# RM_LM25116.net
KiCad netlist of a schematic drawn in Altium Designer
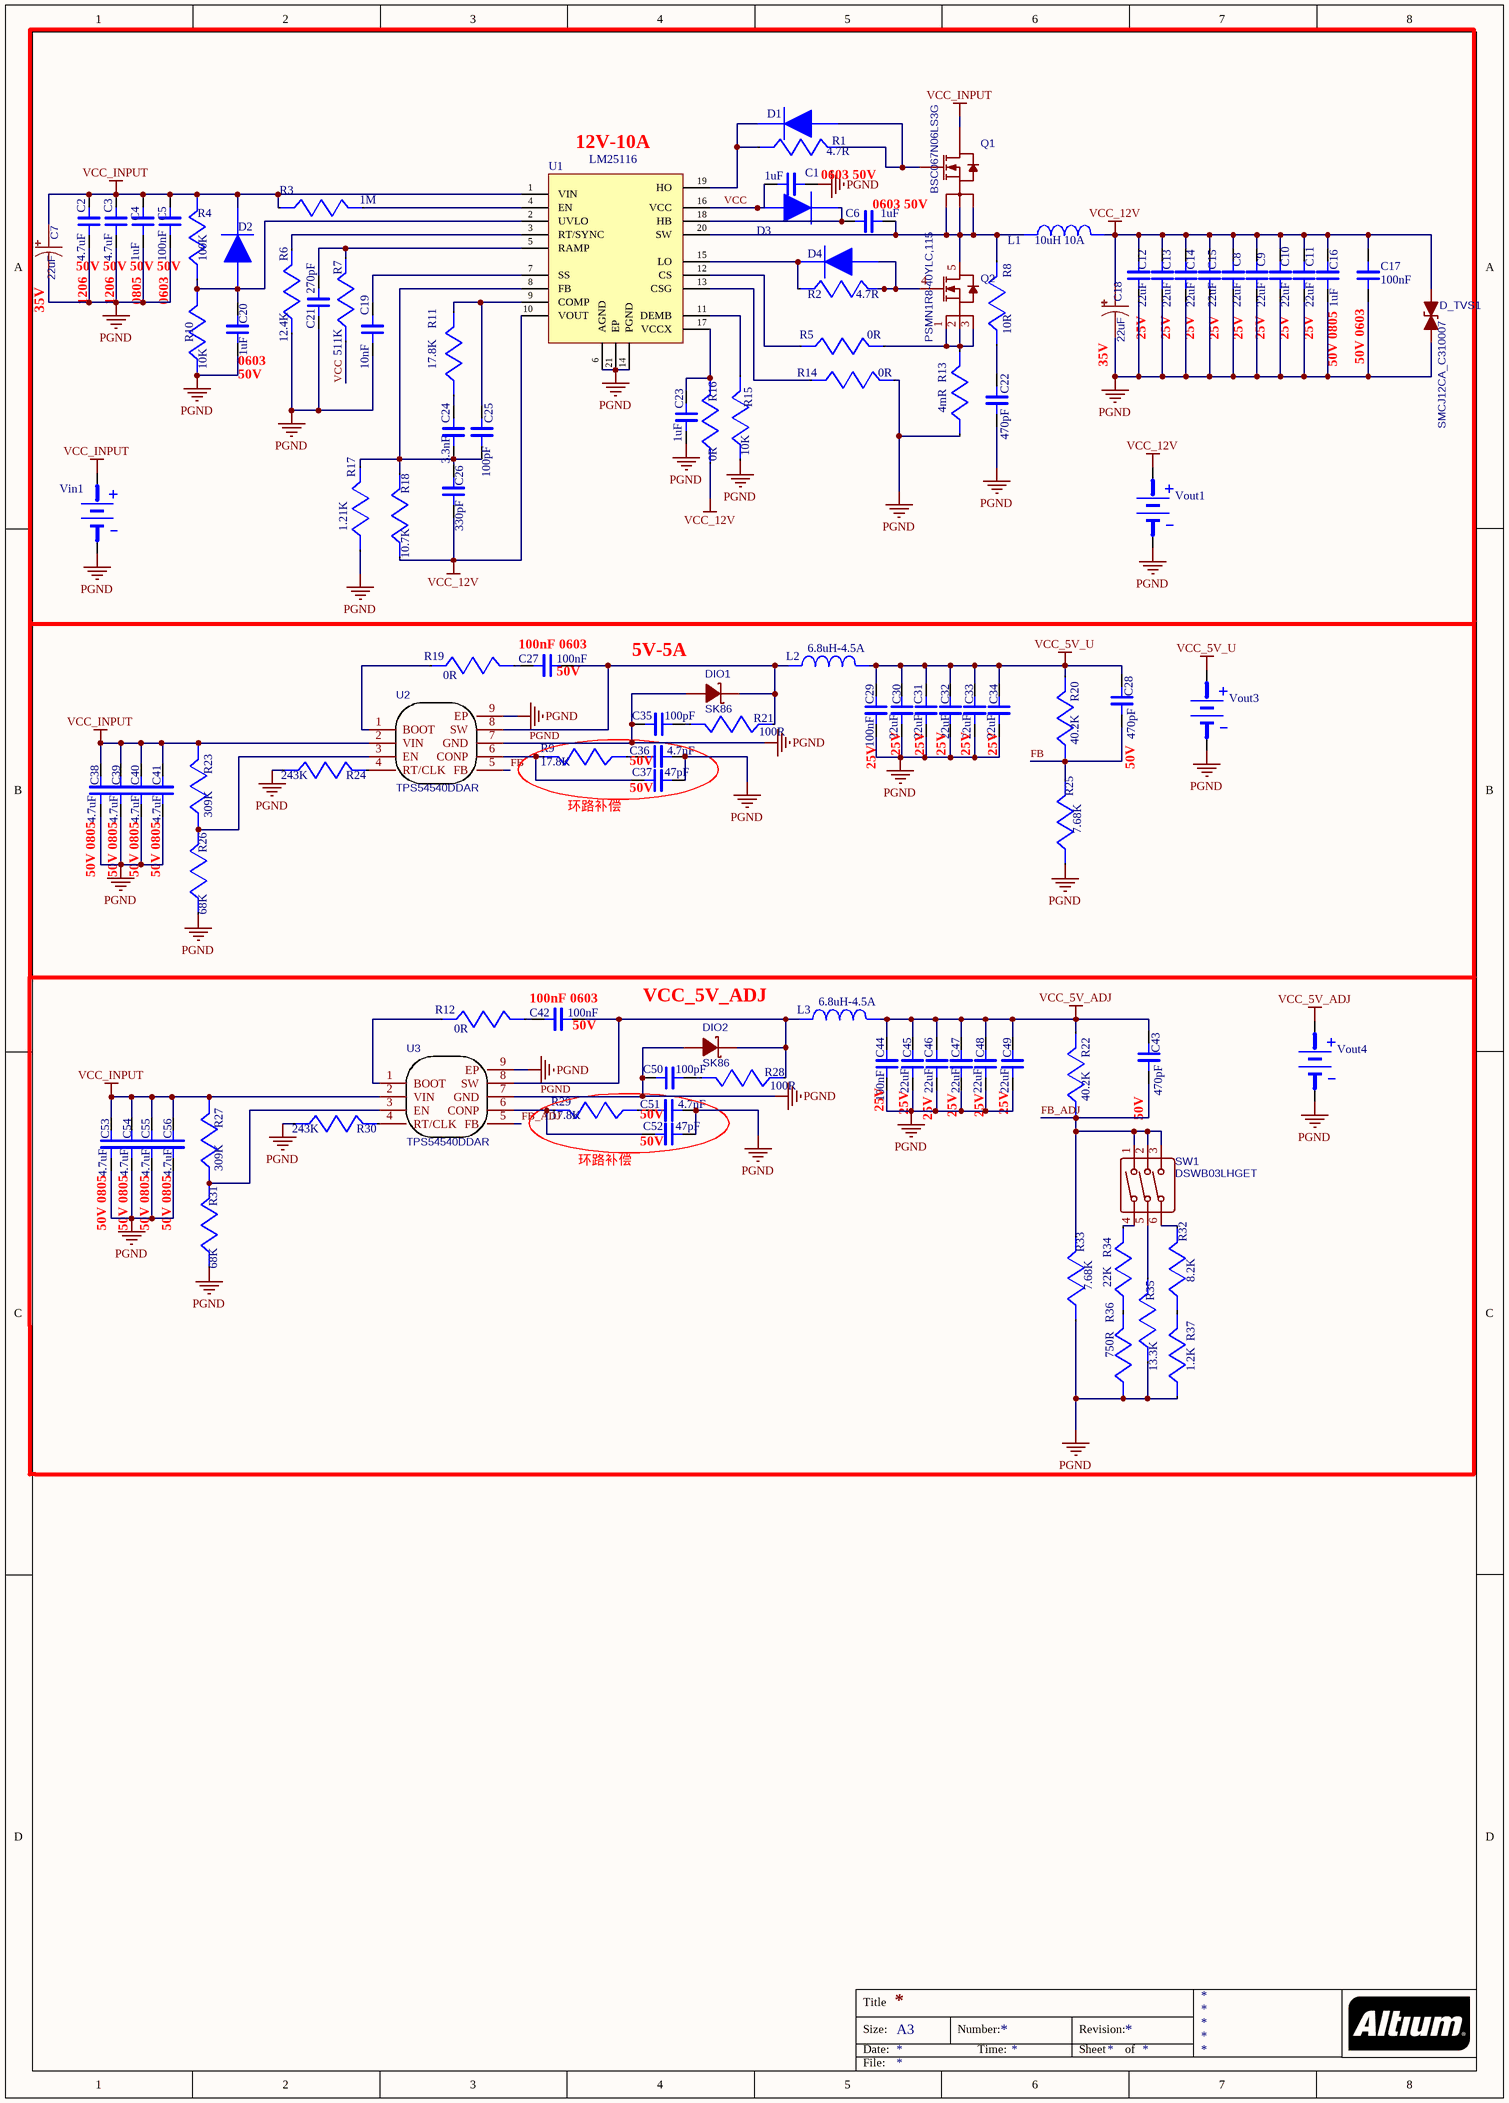
[diagram p0: RM_LM25116.SchDoc]

(export (version "E")
  (design (tool "Eeschema 10.0.6"))
  (components
    (comp (ref "C1")
      (value "1uF")
      (footprint "0603P")
      (description "Capacitor")
      (libsource (lib "lm25116") (part "CAP"))
    )
    (comp (ref "C2")
      (value "4.7uF")
      (footprint "1206")
      (description "Capacitor")
      (libsource (lib "lm25116") (part "CAP"))
    )
    (comp (ref "C3")
      (value "4.7uF")
      (footprint "1206")
      (description "Capacitor")
      (libsource (lib "lm25116") (part "CAP"))
    )
    (comp (ref "C4")
      (value "1uF")
      (footprint "0805")
      (description "Capacitor")
      (libsource (lib "lm25116") (part "CAP"))
    )
    (comp (ref "C5")
      (value "100nF")
      (footprint "0603P")
      (description "Capacitor")
      (libsource (lib "lm25116") (part "CAP"))
    )
    (comp (ref "C6")
      (value "1uF")
      (footprint "0603P")
      (description "Capacitor")
      (libsource (lib "lm25116") (part "CAP"))
    )
    (comp (ref "C7")
      (value "22uF")
      (footprint "22uF")
      (fields
        (field (name "BOM_MANUFACTURER PART") "CA45-D-35V-22μF-K")
        (field (name "BOM_SUPPLIER PART") "C171667")
        (field (name "CONTRIBUTOR") "LCSC")
      )
      (libsource (lib "lm25116") (part "22uF"))
    )
    (comp (ref "C8")
      (value "22uF")
      (footprint "0603P")
      (description "Capacitor")
      (libsource (lib "lm25116") (part "CAP"))
    )
    (comp (ref "C9")
      (value "22uF")
      (footprint "0603P")
      (description "Capacitor")
      (libsource (lib "lm25116") (part "CAP"))
    )
    (comp (ref "C10")
      (value "22uF")
      (footprint "0603P")
      (description "Capacitor")
      (libsource (lib "lm25116") (part "CAP"))
    )
    (comp (ref "C11")
      (value "22uF")
      (footprint "0603P")
      (description "Capacitor")
      (libsource (lib "lm25116") (part "CAP"))
    )
    (comp (ref "C12")
      (value "22uF")
      (footprint "0603P")
      (description "Capacitor")
      (libsource (lib "lm25116") (part "CAP"))
    )
    (comp (ref "C13")
      (value "22uF")
      (footprint "0603P")
      (description "Capacitor")
      (libsource (lib "lm25116") (part "CAP"))
    )
    (comp (ref "C14")
      (value "22uF")
      (footprint "0603P")
      (description "Capacitor")
      (libsource (lib "lm25116") (part "CAP"))
    )
    (comp (ref "C15")
      (value "22uF")
      (footprint "0603P")
      (description "Capacitor")
      (libsource (lib "lm25116") (part "CAP"))
    )
    (comp (ref "C16")
      (value "1uF")
      (footprint "0805")
      (description "Capacitor")
      (libsource (lib "lm25116") (part "CAP"))
    )
    (comp (ref "C17")
      (value "100nF")
      (footprint "0603P")
      (description "Capacitor")
      (libsource (lib "lm25116") (part "CAP"))
    )
    (comp (ref "C18")
      (value "22uF")
      (footprint "22uF")
      (fields
        (field (name "BOM_MANUFACTURER PART") "CA45-D-35V-22μF-K")
        (field (name "BOM_SUPPLIER PART") "C171667")
        (field (name "CONTRIBUTOR") "LCSC")
      )
      (libsource (lib "lm25116") (part "22uF"))
    )
    (comp (ref "C19")
      (value "10nF")
      (footprint "0603P")
      (description "Capacitor")
      (libsource (lib "lm25116") (part "CAP"))
    )
    (comp (ref "C20")
      (value "1uF")
      (footprint "0603P")
      (description "Capacitor")
      (libsource (lib "lm25116") (part "CAP"))
    )
    (comp (ref "C21")
      (value "270pF")
      (footprint "0603P")
      (description "Capacitor")
      (libsource (lib "lm25116") (part "CAP"))
    )
    (comp (ref "C22")
      (value "470pF")
      (footprint "0603P")
      (description "Capacitor")
      (libsource (lib "lm25116") (part "CAP"))
    )
    (comp (ref "C23")
      (value "1uF")
      (footprint "0603P")
      (description "Capacitor")
      (libsource (lib "lm25116") (part "CAP"))
    )
    (comp (ref "C24")
      (value "3.3nF")
      (footprint "0603P")
      (description "Capacitor")
      (libsource (lib "lm25116") (part "CAP"))
    )
    (comp (ref "C25")
      (value "100pF")
      (footprint "0603P")
      (description "Capacitor")
      (libsource (lib "lm25116") (part "CAP"))
    )
    (comp (ref "C26")
      (value "330pF")
      (footprint "0603P")
      (description "Capacitor")
      (libsource (lib "lm25116") (part "CAP"))
    )
    (comp (ref "C27")
      (value "100nF")
      (footprint "0603P")
      (description "Capacitor")
      (libsource (lib "lm25116") (part "CAP"))
    )
    (comp (ref "C28")
      (value "470pF")
      (footprint "0603P")
      (description "Capacitor")
      (libsource (lib "lm25116") (part "CAP"))
    )
    (comp (ref "C29")
      (value "100nF")
      (footprint "0603P")
      (description "Capacitor")
      (libsource (lib "lm25116") (part "CAP"))
    )
    (comp (ref "C30")
      (value "22uF")
      (footprint "0603P")
      (description "Capacitor")
      (libsource (lib "lm25116") (part "CAP"))
    )
    (comp (ref "C31")
      (value "22uF")
      (footprint "0603P")
      (description "Capacitor")
      (libsource (lib "lm25116") (part "CAP"))
    )
    (comp (ref "C32")
      (value "22uF")
      (footprint "0603P")
      (description "Capacitor")
      (libsource (lib "lm25116") (part "CAP"))
    )
    (comp (ref "C33")
      (value "22uF")
      (footprint "0603P")
      (description "Capacitor")
      (libsource (lib "lm25116") (part "CAP"))
    )
    (comp (ref "C34")
      (value "22uF")
      (footprint "0603P")
      (description "Capacitor")
      (libsource (lib "lm25116") (part "CAP"))
    )
    (comp (ref "C35")
      (value "100pF")
      (footprint "0603P")
      (description "Capacitor")
      (libsource (lib "lm25116") (part "CAP"))
    )
    (comp (ref "C36")
      (value "4.7nF")
      (footprint "0603P")
      (description "Capacitor")
      (libsource (lib "lm25116") (part "CAP"))
    )
    (comp (ref "C37")
      (value "47pF")
      (footprint "0603P")
      (description "Capacitor")
      (libsource (lib "lm25116") (part "CAP"))
    )
    (comp (ref "C38")
      (value "4.7uF")
      (footprint "0805")
      (description "Capacitor")
      (libsource (lib "lm25116") (part "CAP"))
    )
    (comp (ref "C39")
      (value "4.7uF")
      (footprint "0805")
      (description "Capacitor")
      (libsource (lib "lm25116") (part "CAP"))
    )
    (comp (ref "C40")
      (value "4.7uF")
      (footprint "0805")
      (description "Capacitor")
      (libsource (lib "lm25116") (part "CAP"))
    )
    (comp (ref "C41")
      (value "4.7uF")
      (footprint "0805")
      (description "Capacitor")
      (libsource (lib "lm25116") (part "CAP"))
    )
    (comp (ref "C42")
      (value "100nF")
      (footprint "0603P")
      (description "Capacitor")
      (libsource (lib "lm25116") (part "CAP"))
    )
    (comp (ref "C43")
      (value "470pF")
      (footprint "0603P")
      (description "Capacitor")
      (libsource (lib "lm25116") (part "CAP"))
    )
    (comp (ref "C44")
      (value "100nF")
      (footprint "0603P")
      (description "Capacitor")
      (libsource (lib "lm25116") (part "CAP"))
    )
    (comp (ref "C45")
      (value "22uF")
      (footprint "0603P")
      (description "Capacitor")
      (libsource (lib "lm25116") (part "CAP"))
    )
    (comp (ref "C46")
      (value "22uF")
      (footprint "0603P")
      (description "Capacitor")
      (libsource (lib "lm25116") (part "CAP"))
    )
    (comp (ref "C47")
      (value "22uF")
      (footprint "0603P")
      (description "Capacitor")
      (libsource (lib "lm25116") (part "CAP"))
    )
    (comp (ref "C48")
      (value "22uF")
      (footprint "0603P")
      (description "Capacitor")
      (libsource (lib "lm25116") (part "CAP"))
    )
    (comp (ref "C49")
      (value "22uF")
      (footprint "0603P")
      (description "Capacitor")
      (libsource (lib "lm25116") (part "CAP"))
    )
    (comp (ref "C50")
      (value "100pF")
      (footprint "0603P")
      (description "Capacitor")
      (libsource (lib "lm25116") (part "CAP"))
    )
    (comp (ref "C51")
      (value "4.7nF")
      (footprint "0603P")
      (description "Capacitor")
      (libsource (lib "lm25116") (part "CAP"))
    )
    (comp (ref "C52")
      (value "47pF")
      (footprint "0603P")
      (description "Capacitor")
      (libsource (lib "lm25116") (part "CAP"))
    )
    (comp (ref "C53")
      (value "4.7uF")
      (footprint "0805")
      (description "Capacitor")
      (libsource (lib "lm25116") (part "CAP"))
    )
    (comp (ref "C54")
      (value "4.7uF")
      (footprint "0805")
      (description "Capacitor")
      (libsource (lib "lm25116") (part "CAP"))
    )
    (comp (ref "C55")
      (value "4.7uF")
      (footprint "0805")
      (description "Capacitor")
      (libsource (lib "lm25116") (part "CAP"))
    )
    (comp (ref "C56")
      (value "4.7uF")
      (footprint "0805")
      (description "Capacitor")
      (libsource (lib "lm25116") (part "CAP"))
    )
    (comp (ref "D1") (value "BAS516,115") (footprint "SOD-523") (libsource (lib "lm25116") (part "D1")))
    (comp (ref "D2") (value "BAS516,115") (footprint "SOD-523") (libsource (lib "lm25116") (part "D1")))
    (comp (ref "D3") (value "BAS516,115") (footprint "SOD-523") (libsource (lib "lm25116") (part "D1")))
    (comp (ref "D4") (value "BAS516,115") (footprint "SOD-523") (libsource (lib "lm25116") (part "D1")))
    (comp (ref "DIO1")
      (value "SK86")
      (footprint "SMC(DO-214AB)")
      (fields (field (name "BOM_SUPPLIER PART") "C64338"))
      (libsource (lib "lm25116") (part "SK86"))
    )
    (comp (ref "DIO2")
      (value "SK86")
      (footprint "SMC(DO-214AB)")
      (fields (field (name "BOM_SUPPLIER PART") "C64338"))
      (libsource (lib "lm25116") (part "SK86"))
    )
    (comp (ref "D_TVS1")
      (value "SMCJ12CA_C310007")
      (footprint "TVS")
      (fields
        (field (name "BOM_SUPPLIER PART") "C310007")
        (field (name "BOM_MANUFACTURER PART") "SMCJ12CA")
        (field (name "CONTRIBUTOR") "LCSC")
      )
      (libsource (lib "lm25116") (part "SMCJ12CA_C310007"))
    )
    (comp (ref "L1")
      (value "10uH 10A")
      (footprint "10uH 10A")
      (description "Unknown")
      (fields (field (name "MANUFACTURER PART NUMBER") "MLC1565-372MLB"))
      (libsource (lib "lm25116") (part "L1"))
    )
    (comp (ref "L2")
      (value "6.8uH-4.5A")
      (footprint "6.8uH 4.5A")
      (description "Unknown")
      (fields (field (name "MANUFACTURER PART NUMBER") "MLC1565-372MLB"))
      (libsource (lib "lm25116") (part "L1"))
    )
    (comp (ref "L3")
      (value "6.8uH-4.5A")
      (footprint "6.8uH 4.5A")
      (description "Unknown")
      (fields (field (name "MANUFACTURER PART NUMBER") "MLC1565-372MLB"))
      (libsource (lib "lm25116") (part "L1"))
    )
    (comp (ref "Q1")
      (value "BSC067N06LS3G")
      (footprint "BSC067N06LS3G")
      (fields (field (name "BOM_SUPPLIER PART") "C24199"))
      (libsource (lib "lm25116") (part "BSC067N06LS3G"))
    )
    (comp (ref "Q2")
      (value "PSMN1R8-40YLC,115")
      (footprint "PSMN1R8-40YLC,115")
      (fields (field (name "BOM_SUPPLIER PART") "C88071"))
      (libsource (lib "lm25116") (part "PSMN1R8-40YLC,115"))
    )
    (comp (ref "R1")
      (value "4.7R")
      (footprint "0603P")
      (description "RES?")
      (libsource (lib "lm25116") (part "RES"))
    )
    (comp (ref "R2")
      (value "4.7R")
      (footprint "0603P")
      (description "RES?")
      (libsource (lib "lm25116") (part "RES"))
    )
    (comp (ref "R3")
      (value "1M")
      (footprint "0603P")
      (description "RES?")
      (libsource (lib "lm25116") (part "RES"))
    )
    (comp (ref "R4")
      (value "100K")
      (footprint "0603P")
      (description "RES?")
      (libsource (lib "lm25116") (part "RES"))
    )
    (comp (ref "R5")
      (value "0R")
      (footprint "0603P")
      (description "RES?")
      (libsource (lib "lm25116") (part "RES"))
    )
    (comp (ref "R6")
      (value "12.4K")
      (footprint "0603P")
      (description "RES?")
      (libsource (lib "lm25116") (part "RES"))
    )
    (comp (ref "R7")
      (value "511K")
      (footprint "0603P")
      (description "RES?")
      (libsource (lib "lm25116") (part "RES"))
    )
    (comp (ref "R8")
      (value "10R")
      (footprint "0603P")
      (description "RES?")
      (libsource (lib "lm25116") (part "RES"))
    )
    (comp (ref "R9")
      (value "17.8K")
      (footprint "0603P")
      (description "RES?")
      (libsource (lib "lm25116") (part "RES"))
    )
    (comp (ref "R10")
      (value "10K")
      (footprint "0603P")
      (description "RES?")
      (libsource (lib "lm25116") (part "RES"))
    )
    (comp (ref "R11")
      (value "17.8K")
      (footprint "0603P")
      (description "RES?")
      (libsource (lib "lm25116") (part "RES"))
    )
    (comp (ref "R12")
      (value "0R")
      (footprint "0603P")
      (description "RES?")
      (libsource (lib "lm25116") (part "RES"))
    )
    (comp (ref "R13")
      (value "4mR")
      (footprint "LC-2512_L")
      (description "RES?")
      (libsource (lib "lm25116") (part "RES"))
    )
    (comp (ref "R14")
      (value "0R")
      (footprint "0603P")
      (description "RES?")
      (libsource (lib "lm25116") (part "RES"))
    )
    (comp (ref "R15")
      (value "10K")
      (footprint "0603P")
      (description "RES?")
      (libsource (lib "lm25116") (part "RES"))
    )
    (comp (ref "R16")
      (value "0R")
      (footprint "0603P")
      (description "RES?")
      (libsource (lib "lm25116") (part "RES"))
    )
    (comp (ref "R17")
      (value "1.21K")
      (footprint "0603P")
      (description "RES?")
      (libsource (lib "lm25116") (part "RES"))
    )
    (comp (ref "R18")
      (value "10.7K")
      (footprint "0603P")
      (description "RES?")
      (libsource (lib "lm25116") (part "RES"))
    )
    (comp (ref "R19")
      (value "0R")
      (footprint "0603P")
      (description "RES?")
      (libsource (lib "lm25116") (part "RES"))
    )
    (comp (ref "R20")
      (value "40.2K")
      (footprint "0603P")
      (description "RES?")
      (libsource (lib "lm25116") (part "RES"))
    )
    (comp (ref "R21")
      (value "100R")
      (footprint "0603P")
      (description "RES?")
      (libsource (lib "lm25116") (part "RES"))
    )
    (comp (ref "R22")
      (value "40.2K")
      (footprint "0603P")
      (description "RES?")
      (libsource (lib "lm25116") (part "RES"))
    )
    (comp (ref "R23")
      (value "309K")
      (footprint "0603P")
      (description "RES?")
      (libsource (lib "lm25116") (part "RES"))
    )
    (comp (ref "R24")
      (value "243K")
      (footprint "0603P")
      (description "RES?")
      (libsource (lib "lm25116") (part "RES"))
    )
    (comp (ref "R25")
      (value "7.68K")
      (footprint "0603P")
      (description "RES?")
      (libsource (lib "lm25116") (part "RES"))
    )
    (comp (ref "R26")
      (value "68K")
      (footprint "0603P")
      (description "RES?")
      (libsource (lib "lm25116") (part "RES"))
    )
    (comp (ref "R27")
      (value "309K")
      (footprint "0603P")
      (description "RES?")
      (libsource (lib "lm25116") (part "RES"))
    )
    (comp (ref "R28")
      (value "100R")
      (footprint "0603P")
      (description "RES?")
      (libsource (lib "lm25116") (part "RES"))
    )
    (comp (ref "R29")
      (value "17.8K")
      (footprint "0603P")
      (description "RES?")
      (libsource (lib "lm25116") (part "RES"))
    )
    (comp (ref "R30")
      (value "243K")
      (footprint "0603P")
      (description "RES?")
      (libsource (lib "lm25116") (part "RES"))
    )
    (comp (ref "R31")
      (value "68K")
      (footprint "0603P")
      (description "RES?")
      (libsource (lib "lm25116") (part "RES"))
    )
    (comp (ref "R32")
      (value "8.2K")
      (footprint "0603P")
      (description "R")
      (libsource (lib "lm25116") (part "RES"))
    )
    (comp (ref "R33")
      (value "7.68K")
      (footprint "0603P")
      (description "RES?")
      (libsource (lib "lm25116") (part "RES"))
    )
    (comp (ref "R34")
      (value "22K")
      (footprint "0603P")
      (description "R")
      (libsource (lib "lm25116") (part "RES"))
    )
    (comp (ref "R35")
      (value "13.3K")
      (footprint "0603P")
      (description "R")
      (libsource (lib "lm25116") (part "RES"))
    )
    (comp (ref "R36") (value "750R") (footprint "0603P") (libsource (lib "lm25116") (part "RES")))
    (comp (ref "R37")
      (value "1.2K")
      (footprint "0603P")
      (description "R")
      (libsource (lib "lm25116") (part "RES"))
    )
    (comp (ref "SW1")
      (value "DSWB03LHGET")
      (footprint "lm25116:CH3_SWITCH")
      (fields (field (name "BOM_SUPPLIER PART") "C99420") (field (name "CONTRIBUTOR") "LCSC"))
      (libsource (lib "lm25116") (part "DSWB03LHGET"))
    )
    (comp (ref "U1")
      (value "LM25116")
      (footprint "lm25116:MXA20A")
      (libsource (lib "lm25116") (part "LM25116"))
    )
    (comp (ref "U2")
      (value "TPS54540DDAR")
      (footprint "lm25116:TPS54540")
      (fields (field (name "BOM_SUPPLIER PART") "C95286"))
      (libsource (lib "lm25116") (part "TPS54540DDAR"))
    )
    (comp (ref "U3")
      (value "TPS54540DDAR")
      (footprint "lm25116:TPS54540")
      (fields (field (name "BOM_SUPPLIER PART") "C95286"))
      (libsource (lib "lm25116") (part "TPS54540DDAR"))
    )
    (comp (ref "Vin1") (value "WB_BATTERY") (footprint "XT30_PW母头") (libsource (lib "lm25116") (part "Vin")))
    (comp (ref "Vout1")
      (value "Vout")
      (footprint "lm25116:XT30_PW公头")
      (description "BATTERY")
      (fields (field (name "MANUFACTURER PART NUMBER") "WB_BATTERY"))
      (libsource (lib "lm25116") (part "Vout"))
    )
    (comp (ref "Vout3")
      (value "Vout")
      (footprint "lm25116:XT30_PW公头")
      (description "BATTERY")
      (fields (field (name "MANUFACTURER PART NUMBER") "WB_BATTERY"))
      (libsource (lib "lm25116") (part "Vout"))
    )
    (comp (ref "Vout4")
      (value "Vout")
      (footprint "lm25116:XT30_PW公头")
      (description "BATTERY")
      (fields (field (name "MANUFACTURER PART NUMBER") "WB_BATTERY"))
      (libsource (lib "lm25116") (part "Vout"))
    )
  )
  (nets
    (net (code "1") (name "/FB") (class "Default")
      (node (ref "C28") (pin "1") (pinfunction "1_1") (pintype "passive"))
      (node (ref "R20") (pin "1") (pinfunction "1_1") (pintype "passive"))
      (node (ref "R25") (pin "2") (pinfunction "2_2") (pintype "passive"))
      (node (ref "U2") (pin "5") (pinfunction "FB_5") (pintype "passive"))
    )
    (net (code "2") (name "/FB_ADJ") (class "Default")
      (node (ref "C43") (pin "1") (pinfunction "1_1") (pintype "passive"))
      (node (ref "R22") (pin "1") (pinfunction "1_1") (pintype "passive"))
      (node (ref "R33") (pin "2") (pinfunction "2_2") (pintype "passive"))
      (node (ref "SW1") (pin "1") (pinfunction "1_1") (pintype "passive"))
      (node (ref "SW1") (pin "2") (pinfunction "2_2") (pintype "passive"))
      (node (ref "SW1") (pin "3") (pinfunction "3_3") (pintype "passive"))
      (node (ref "U3") (pin "5") (pinfunction "FB_5") (pintype "passive"))
    )
    (net (code "3") (name "/VCC") (class "Default")
      (node (ref "C1") (pin "1") (pinfunction "1_1") (pintype "passive"))
      (node (ref "D3") (pin "2") (pinfunction "A_2") (pintype "passive"))
      (node (ref "R7") (pin "1") (pinfunction "1_1") (pintype "passive"))
      (node (ref "U1") (pin "16") (pinfunction "VCC_16") (pintype "passive"))
    )
    (net (code "4") (name "Net-(C22-Pad2)") (class "Default")
      (node (ref "C22") (pin "2") (pinfunction "2_2") (pintype "passive"))
      (node (ref "R8") (pin "1") (pinfunction "1_1") (pintype "passive"))
    )
    (net (code "5") (name "Net-(C24-Pad1)") (class "Default")
      (node (ref "C24") (pin "1") (pinfunction "1_1") (pintype "passive"))
      (node (ref "R11") (pin "1") (pinfunction "1_1") (pintype "passive"))
    )
    (net (code "6") (name "Net-(C27-Pad1)") (class "Default")
      (node (ref "C27") (pin "1") (pinfunction "1_1") (pintype "passive"))
      (node (ref "R19") (pin "2") (pinfunction "2_2") (pintype "passive"))
    )
    (net (code "7") (name "Net-(C35-Pad1)") (class "Default")
      (node (ref "C35") (pin "1") (pinfunction "1_1") (pintype "passive"))
      (node (ref "R21") (pin "2") (pinfunction "2_2") (pintype "passive"))
    )
    (net (code "8") (name "Net-(C36-Pad1)") (class "Default")
      (node (ref "C36") (pin "1") (pinfunction "1_1") (pintype "passive"))
      (node (ref "R9") (pin "1") (pinfunction "1_1") (pintype "passive"))
    )
    (net (code "9") (name "Net-(C42-Pad1)") (class "Default")
      (node (ref "C42") (pin "1") (pinfunction "1_1") (pintype "passive"))
      (node (ref "R12") (pin "2") (pinfunction "2_2") (pintype "passive"))
    )
    (net (code "10") (name "Net-(C50-Pad1)") (class "Default")
      (node (ref "C50") (pin "1") (pinfunction "1_1") (pintype "passive"))
      (node (ref "R28") (pin "2") (pinfunction "2_2") (pintype "passive"))
    )
    (net (code "11") (name "Net-(C51-Pad1)") (class "Default")
      (node (ref "C51") (pin "1") (pinfunction "1_1") (pintype "passive"))
      (node (ref "R29") (pin "1") (pinfunction "1_1") (pintype "passive"))
    )
    (net (code "12") (name "Net-(D1-A)") (class "Default")
      (node (ref "D1") (pin "2") (pinfunction "A_2") (pintype "passive"))
      (node (ref "Q1") (pin "4") (pinfunction "G_4") (pintype "passive"))
      (node (ref "R1") (pin "2") (pinfunction "2_2") (pintype "passive"))
    )
    (net (code "13") (name "Net-(D1-K)") (class "Default")
      (node (ref "D1") (pin "1") (pinfunction "K_1") (pintype "passive"))
      (node (ref "R1") (pin "1") (pinfunction "1_1") (pintype "passive"))
      (node (ref "U1") (pin "19") (pinfunction "HO_19") (pintype "passive"))
    )
    (net (code "14") (name "Net-(D2-A)") (class "Default")
      (node (ref "C20") (pin "2") (pinfunction "2_2") (pintype "passive"))
      (node (ref "D2") (pin "2") (pinfunction "A_2") (pintype "passive"))
      (node (ref "R10") (pin "2") (pinfunction "2_2") (pintype "passive"))
      (node (ref "R4") (pin "1") (pinfunction "1_1") (pintype "passive"))
      (node (ref "U1") (pin "2") (pinfunction "UVLO_2") (pintype "passive"))
    )
    (net (code "15") (name "Net-(D3-K)") (class "Default")
      (node (ref "C6") (pin "1") (pinfunction "1_1") (pintype "passive"))
      (node (ref "D3") (pin "1") (pinfunction "K_1") (pintype "passive"))
      (node (ref "U1") (pin "18") (pinfunction "HB_18") (pintype "passive"))
    )
    (net (code "16") (name "Net-(D4-A)") (class "Default")
      (node (ref "D4") (pin "2") (pinfunction "A_2") (pintype "passive"))
      (node (ref "Q2") (pin "4") (pinfunction "G_4") (pintype "passive"))
      (node (ref "R2") (pin "2") (pinfunction "2_2") (pintype "passive"))
    )
    (net (code "17") (name "Net-(D4-K)") (class "Default")
      (node (ref "D4") (pin "1") (pinfunction "K_1") (pintype "passive"))
      (node (ref "R2") (pin "1") (pinfunction "1_1") (pintype "passive"))
      (node (ref "U1") (pin "15") (pinfunction "LO_15") (pintype "passive"))
    )
    (net (code "18") (name "Net-(DIO1-K)") (class "Default")
      (node (ref "C27") (pin "2") (pinfunction "2_2") (pintype "passive"))
      (node (ref "DIO1") (pin "2") (pinfunction "K_2") (pintype "passive"))
      (node (ref "L2") (pin "1") (pinfunction "1_1") (pintype "passive"))
      (node (ref "R21") (pin "1") (pinfunction "1_1") (pintype "passive"))
      (node (ref "U2") (pin "8") (pinfunction "SW_8") (pintype "passive"))
    )
    (net (code "19") (name "Net-(DIO2-K)") (class "Default")
      (node (ref "C42") (pin "2") (pinfunction "2_2") (pintype "passive"))
      (node (ref "DIO2") (pin "2") (pinfunction "K_2") (pintype "passive"))
      (node (ref "L3") (pin "1") (pinfunction "1_1") (pintype "passive"))
      (node (ref "R28") (pin "1") (pinfunction "1_1") (pintype "passive"))
      (node (ref "U3") (pin "8") (pinfunction "SW_8") (pintype "passive"))
    )
    (net (code "20") (name "Net-(Q2-D)") (class "Default")
      (node (ref "C6") (pin "2") (pinfunction "2_2") (pintype "passive"))
      (node (ref "L1") (pin "1") (pinfunction "1_1") (pintype "passive"))
      (node (ref "Q1") (pin "1") (pinfunction "S_1") (pintype "passive"))
      (node (ref "Q1") (pin "2") (pinfunction "S_2") (pintype "passive"))
      (node (ref "Q1") (pin "3") (pinfunction "S_3") (pintype "passive"))
      (node (ref "Q2") (pin "5") (pinfunction "D_5") (pintype "passive"))
      (node (ref "R8") (pin "2") (pinfunction "2_2") (pintype "passive"))
      (node (ref "U1") (pin "20") (pinfunction "SW_20") (pintype "passive"))
    )
    (net (code "21") (name "Net-(Q2-S-Pad1)") (class "Default")
      (node (ref "Q2") (pin "1") (pinfunction "S_1") (pintype "passive"))
      (node (ref "Q2") (pin "2") (pinfunction "S_2") (pintype "passive"))
      (node (ref "Q2") (pin "3") (pinfunction "S_3") (pintype "passive"))
      (node (ref "R13") (pin "2") (pinfunction "2_2") (pintype "passive"))
      (node (ref "R5") (pin "2") (pinfunction "2_2") (pintype "passive"))
    )
    (net (code "22") (name "Net-(R32-Pad1)") (class "Default")
      (node (ref "R32") (pin "1") (pinfunction "1_1") (pintype "passive"))
      (node (ref "R37") (pin "2") (pinfunction "2_2") (pintype "passive"))
    )
    (net (code "23") (name "Net-(R32-Pad2)") (class "Default")
      (node (ref "R32") (pin "2") (pinfunction "2_2") (pintype "passive"))
      (node (ref "SW1") (pin "6") (pinfunction "6_6") (pintype "passive"))
    )
    (net (code "24") (name "Net-(R34-Pad1)") (class "Default")
      (node (ref "R34") (pin "1") (pinfunction "1_1") (pintype "passive"))
      (node (ref "R36") (pin "2") (pinfunction "2_2") (pintype "passive"))
    )
    (net (code "25") (name "Net-(R34-Pad2)") (class "Default")
      (node (ref "R34") (pin "2") (pinfunction "2_2") (pintype "passive"))
      (node (ref "SW1") (pin "4") (pinfunction "4_4") (pintype "passive"))
    )
    (net (code "26") (name "Net-(R35-Pad2)") (class "Default")
      (node (ref "R35") (pin "2") (pinfunction "2_2") (pintype "passive"))
      (node (ref "SW1") (pin "5") (pinfunction "5_5") (pintype "passive"))
    )
    (net (code "27") (name "Net-(U1-COMP)") (class "Default")
      (node (ref "C25") (pin "1") (pinfunction "1_1") (pintype "passive"))
      (node (ref "R11") (pin "2") (pinfunction "2_2") (pintype "passive"))
      (node (ref "U1") (pin "9") (pinfunction "COMP_9") (pintype "passive"))
    )
    (net (code "28") (name "Net-(U1-CS)") (class "Default")
      (node (ref "R5") (pin "1") (pinfunction "1_1") (pintype "passive"))
      (node (ref "U1") (pin "12") (pinfunction "CS_12") (pintype "passive"))
    )
    (net (code "29") (name "Net-(U1-CSG)") (class "Default")
      (node (ref "R14") (pin "1") (pinfunction "1_1") (pintype "passive"))
      (node (ref "U1") (pin "13") (pinfunction "CSG_13") (pintype "passive"))
    )
    (net (code "30") (name "Net-(U1-DEMB)") (class "Default")
      (node (ref "R15") (pin "2") (pinfunction "2_2") (pintype "passive"))
      (node (ref "U1") (pin "11") (pinfunction "DEMB_11") (pintype "passive"))
    )
    (net (code "31") (name "Net-(U1-EN)") (class "Default")
      (node (ref "R3") (pin "2") (pinfunction "2_2") (pintype "passive"))
      (node (ref "U1") (pin "4") (pinfunction "EN_4") (pintype "passive"))
    )
    (net (code "32") (name "Net-(U1-FB)") (class "Default")
      (node (ref "C24") (pin "2") (pinfunction "2_2") (pintype "passive"))
      (node (ref "C25") (pin "2") (pinfunction "2_2") (pintype "passive"))
      (node (ref "C26") (pin "2") (pinfunction "2_2") (pintype "passive"))
      (node (ref "R17") (pin "2") (pinfunction "2_2") (pintype "passive"))
      (node (ref "R18") (pin "2") (pinfunction "2_2") (pintype "passive"))
      (node (ref "U1") (pin "8") (pinfunction "FB_8") (pintype "passive"))
    )
    (net (code "33") (name "Net-(U1-RAMP)") (class "Default")
      (node (ref "C21") (pin "2") (pinfunction "2_2") (pintype "passive"))
      (node (ref "R7") (pin "2") (pinfunction "2_2") (pintype "passive"))
      (node (ref "U1") (pin "5") (pinfunction "RAMP_5") (pintype "passive"))
    )
    (net (code "34") (name "Net-(U1-RT{slash}SYNC)") (class "Default")
      (node (ref "R6") (pin "2") (pinfunction "2_2") (pintype "passive"))
      (node (ref "U1") (pin "3") (pinfunction "RT/SYNC_3") (pintype "passive"))
    )
    (net (code "35") (name "Net-(U1-SS)") (class "Default")
      (node (ref "C19") (pin "2") (pinfunction "2_2") (pintype "passive"))
      (node (ref "U1") (pin "7") (pinfunction "SS_7") (pintype "passive"))
    )
    (net (code "36") (name "Net-(U1-VCCX)") (class "Default")
      (node (ref "C23") (pin "2") (pinfunction "2_2") (pintype "passive"))
      (node (ref "R16") (pin "2") (pinfunction "2_2") (pintype "passive"))
      (node (ref "U1") (pin "17") (pinfunction "VCCX_17") (pintype "passive"))
    )
    (net (code "37") (name "Net-(U2-BOOT)") (class "Default")
      (node (ref "R19") (pin "1") (pinfunction "1_1") (pintype "passive"))
      (node (ref "U2") (pin "1") (pinfunction "BOOT_1") (pintype "passive"))
    )
    (net (code "38") (name "Net-(U2-CONP)") (class "Default")
      (node (ref "C37") (pin "1") (pinfunction "1_1") (pintype "passive"))
      (node (ref "R9") (pin "2") (pinfunction "2_2") (pintype "passive"))
      (node (ref "U2") (pin "6") (pinfunction "CONP_6") (pintype "passive"))
    )
    (net (code "39") (name "Net-(U2-EN)") (class "Default")
      (node (ref "R23") (pin "1") (pinfunction "1_1") (pintype "passive"))
      (node (ref "R26") (pin "2") (pinfunction "2_2") (pintype "passive"))
      (node (ref "U2") (pin "3") (pinfunction "EN_3") (pintype "passive"))
    )
    (net (code "40") (name "Net-(U2-RT{slash}CLK)") (class "Default")
      (node (ref "R24") (pin "2") (pinfunction "2_2") (pintype "passive"))
      (node (ref "U2") (pin "4") (pinfunction "RT/CLK_4") (pintype "passive"))
    )
    (net (code "41") (name "Net-(U3-BOOT)") (class "Default")
      (node (ref "R12") (pin "1") (pinfunction "1_1") (pintype "passive"))
      (node (ref "U3") (pin "1") (pinfunction "BOOT_1") (pintype "passive"))
    )
    (net (code "42") (name "Net-(U3-CONP)") (class "Default")
      (node (ref "C52") (pin "1") (pinfunction "1_1") (pintype "passive"))
      (node (ref "R29") (pin "2") (pinfunction "2_2") (pintype "passive"))
      (node (ref "U3") (pin "6") (pinfunction "CONP_6") (pintype "passive"))
    )
    (net (code "43") (name "Net-(U3-EN)") (class "Default")
      (node (ref "R27") (pin "1") (pinfunction "1_1") (pintype "passive"))
      (node (ref "R31") (pin "2") (pinfunction "2_2") (pintype "passive"))
      (node (ref "U3") (pin "3") (pinfunction "EN_3") (pintype "passive"))
    )
    (net (code "44") (name "Net-(U3-RT{slash}CLK)") (class "Default")
      (node (ref "R30") (pin "2") (pinfunction "2_2") (pintype "passive"))
      (node (ref "U3") (pin "4") (pinfunction "RT/CLK_4") (pintype "passive"))
    )
    (net (code "45") (name "PGND") (class "Default")
      (node (ref "C1") (pin "2") (pinfunction "2_2") (pintype "passive"))
      (node (ref "C10") (pin "1") (pinfunction "1_1") (pintype "passive"))
      (node (ref "C11") (pin "1") (pinfunction "1_1") (pintype "passive"))
      (node (ref "C12") (pin "1") (pinfunction "1_1") (pintype "passive"))
      (node (ref "C13") (pin "1") (pinfunction "1_1") (pintype "passive"))
      (node (ref "C14") (pin "1") (pinfunction "1_1") (pintype "passive"))
      (node (ref "C15") (pin "1") (pinfunction "1_1") (pintype "passive"))
      (node (ref "C16") (pin "1") (pinfunction "1_1") (pintype "passive"))
      (node (ref "C17") (pin "1") (pinfunction "1_1") (pintype "passive"))
      (node (ref "C18") (pin "2") (pinfunction "2_2") (pintype "passive"))
      (node (ref "C19") (pin "1") (pinfunction "1_1") (pintype "passive"))
      (node (ref "C2") (pin "1") (pinfunction "1_1") (pintype "passive"))
      (node (ref "C20") (pin "1") (pinfunction "1_1") (pintype "passive"))
      (node (ref "C21") (pin "1") (pinfunction "1_1") (pintype "passive"))
      (node (ref "C22") (pin "1") (pinfunction "1_1") (pintype "passive"))
      (node (ref "C23") (pin "1") (pinfunction "1_1") (pintype "passive"))
      (node (ref "C29") (pin "1") (pinfunction "1_1") (pintype "passive"))
      (node (ref "C3") (pin "1") (pinfunction "1_1") (pintype "passive"))
      (node (ref "C30") (pin "1") (pinfunction "1_1") (pintype "passive"))
      (node (ref "C31") (pin "1") (pinfunction "1_1") (pintype "passive"))
      (node (ref "C32") (pin "1") (pinfunction "1_1") (pintype "passive"))
      (node (ref "C33") (pin "1") (pinfunction "1_1") (pintype "passive"))
      (node (ref "C34") (pin "1") (pinfunction "1_1") (pintype "passive"))
      (node (ref "C35") (pin "2") (pinfunction "2_2") (pintype "passive"))
      (node (ref "C36") (pin "2") (pinfunction "2_2") (pintype "passive"))
      (node (ref "C37") (pin "2") (pinfunction "2_2") (pintype "passive"))
      (node (ref "C38") (pin "1") (pinfunction "1_1") (pintype "passive"))
      (node (ref "C39") (pin "1") (pinfunction "1_1") (pintype "passive"))
      (node (ref "C4") (pin "1") (pinfunction "1_1") (pintype "passive"))
      (node (ref "C40") (pin "1") (pinfunction "1_1") (pintype "passive"))
      (node (ref "C41") (pin "1") (pinfunction "1_1") (pintype "passive"))
      (node (ref "C44") (pin "1") (pinfunction "1_1") (pintype "passive"))
      (node (ref "C45") (pin "1") (pinfunction "1_1") (pintype "passive"))
      (node (ref "C46") (pin "1") (pinfunction "1_1") (pintype "passive"))
      (node (ref "C47") (pin "1") (pinfunction "1_1") (pintype "passive"))
      (node (ref "C48") (pin "1") (pinfunction "1_1") (pintype "passive"))
      (node (ref "C49") (pin "1") (pinfunction "1_1") (pintype "passive"))
      (node (ref "C5") (pin "1") (pinfunction "1_1") (pintype "passive"))
      (node (ref "C50") (pin "2") (pinfunction "2_2") (pintype "passive"))
      (node (ref "C51") (pin "2") (pinfunction "2_2") (pintype "passive"))
      (node (ref "C52") (pin "2") (pinfunction "2_2") (pintype "passive"))
      (node (ref "C53") (pin "1") (pinfunction "1_1") (pintype "passive"))
      (node (ref "C54") (pin "1") (pinfunction "1_1") (pintype "passive"))
      (node (ref "C55") (pin "1") (pinfunction "1_1") (pintype "passive"))
      (node (ref "C56") (pin "1") (pinfunction "1_1") (pintype "passive"))
      (node (ref "C7") (pin "2") (pinfunction "2_2") (pintype "passive"))
      (node (ref "C8") (pin "1") (pinfunction "1_1") (pintype "passive"))
      (node (ref "C9") (pin "1") (pinfunction "1_1") (pintype "passive"))
      (node (ref "DIO1") (pin "1") (pinfunction "A_1") (pintype "passive"))
      (node (ref "DIO2") (pin "1") (pinfunction "A_1") (pintype "passive"))
      (node (ref "D_TVS1") (pin "1") (pinfunction "K_1") (pintype "passive"))
      (node (ref "R10") (pin "1") (pinfunction "1_1") (pintype "passive"))
      (node (ref "R13") (pin "1") (pinfunction "1_1") (pintype "passive"))
      (node (ref "R14") (pin "2") (pinfunction "2_2") (pintype "passive"))
      (node (ref "R15") (pin "1") (pinfunction "1_1") (pintype "passive"))
      (node (ref "R17") (pin "1") (pinfunction "1_1") (pintype "passive"))
      (node (ref "R24") (pin "1") (pinfunction "1_1") (pintype "passive"))
      (node (ref "R25") (pin "1") (pinfunction "1_1") (pintype "passive"))
      (node (ref "R26") (pin "1") (pinfunction "1_1") (pintype "passive"))
      (node (ref "R30") (pin "1") (pinfunction "1_1") (pintype "passive"))
      (node (ref "R31") (pin "1") (pinfunction "1_1") (pintype "passive"))
      (node (ref "R33") (pin "1") (pinfunction "1_1") (pintype "passive"))
      (node (ref "R35") (pin "1") (pinfunction "1_1") (pintype "passive"))
      (node (ref "R36") (pin "1") (pinfunction "1_1") (pintype "passive"))
      (node (ref "R37") (pin "1") (pinfunction "1_1") (pintype "passive"))
      (node (ref "R6") (pin "1") (pinfunction "1_1") (pintype "passive"))
      (node (ref "U1") (pin "14") (pinfunction "PGND_14") (pintype "passive"))
      (node (ref "U1") (pin "21") (pinfunction "EP_21") (pintype "passive"))
      (node (ref "U1") (pin "6") (pinfunction "AGND_6") (pintype "passive"))
      (node (ref "U2") (pin "7") (pinfunction "GND_7") (pintype "passive"))
      (node (ref "U2") (pin "9") (pinfunction "EP_9") (pintype "passive"))
      (node (ref "U3") (pin "7") (pinfunction "GND_7") (pintype "passive"))
      (node (ref "U3") (pin "9") (pinfunction "EP_9") (pintype "passive"))
      (node (ref "Vin1") (pin "2") (pinfunction "-_2") (pintype "passive"))
      (node (ref "Vout1") (pin "2") (pinfunction "-_2") (pintype "passive"))
      (node (ref "Vout3") (pin "2") (pinfunction "-_2") (pintype "passive"))
      (node (ref "Vout4") (pin "2") (pinfunction "-_2") (pintype "passive"))
    )
    (net (code "46") (name "VCC_5V_ADJ") (class "Default")
      (node (ref "C43") (pin "2") (pinfunction "2_2") (pintype "passive"))
      (node (ref "C44") (pin "2") (pinfunction "2_2") (pintype "passive"))
      (node (ref "C45") (pin "2") (pinfunction "2_2") (pintype "passive"))
      (node (ref "C46") (pin "2") (pinfunction "2_2") (pintype "passive"))
      (node (ref "C47") (pin "2") (pinfunction "2_2") (pintype "passive"))
      (node (ref "C48") (pin "2") (pinfunction "2_2") (pintype "passive"))
      (node (ref "C49") (pin "2") (pinfunction "2_2") (pintype "passive"))
      (node (ref "L3") (pin "2") (pinfunction "2_2") (pintype "passive"))
      (node (ref "R22") (pin "2") (pinfunction "2_2") (pintype "passive"))
      (node (ref "Vout4") (pin "1") (pinfunction "+_1") (pintype "passive"))
    )
    (net (code "47") (name "VCC_5V_U") (class "Default")
      (node (ref "C28") (pin "2") (pinfunction "2_2") (pintype "passive"))
      (node (ref "C29") (pin "2") (pinfunction "2_2") (pintype "passive"))
      (node (ref "C30") (pin "2") (pinfunction "2_2") (pintype "passive"))
      (node (ref "C31") (pin "2") (pinfunction "2_2") (pintype "passive"))
      (node (ref "C32") (pin "2") (pinfunction "2_2") (pintype "passive"))
      (node (ref "C33") (pin "2") (pinfunction "2_2") (pintype "passive"))
      (node (ref "C34") (pin "2") (pinfunction "2_2") (pintype "passive"))
      (node (ref "L2") (pin "2") (pinfunction "2_2") (pintype "passive"))
      (node (ref "R20") (pin "2") (pinfunction "2_2") (pintype "passive"))
      (node (ref "Vout3") (pin "1") (pinfunction "+_1") (pintype "passive"))
    )
    (net (code "48") (name "VCC_12V") (class "Default")
      (node (ref "C10") (pin "2") (pinfunction "2_2") (pintype "passive"))
      (node (ref "C11") (pin "2") (pinfunction "2_2") (pintype "passive"))
      (node (ref "C12") (pin "2") (pinfunction "2_2") (pintype "passive"))
      (node (ref "C13") (pin "2") (pinfunction "2_2") (pintype "passive"))
      (node (ref "C14") (pin "2") (pinfunction "2_2") (pintype "passive"))
      (node (ref "C15") (pin "2") (pinfunction "2_2") (pintype "passive"))
      (node (ref "C16") (pin "2") (pinfunction "2_2") (pintype "passive"))
      (node (ref "C17") (pin "2") (pinfunction "2_2") (pintype "passive"))
      (node (ref "C18") (pin "1") (pinfunction "1_1") (pintype "passive"))
      (node (ref "C26") (pin "1") (pinfunction "1_1") (pintype "passive"))
      (node (ref "C8") (pin "2") (pinfunction "2_2") (pintype "passive"))
      (node (ref "C9") (pin "2") (pinfunction "2_2") (pintype "passive"))
      (node (ref "D_TVS1") (pin "2") (pinfunction "A_2") (pintype "passive"))
      (node (ref "L1") (pin "2") (pinfunction "2_2") (pintype "passive"))
      (node (ref "R16") (pin "1") (pinfunction "1_1") (pintype "passive"))
      (node (ref "R18") (pin "1") (pinfunction "1_1") (pintype "passive"))
      (node (ref "U1") (pin "10") (pinfunction "VOUT_10") (pintype "passive"))
      (node (ref "Vout1") (pin "1") (pinfunction "+_1") (pintype "passive"))
    )
    (net (code "49") (name "VCC_INPUT") (class "Default")
      (node (ref "C2") (pin "2") (pinfunction "2_2") (pintype "passive"))
      (node (ref "C3") (pin "2") (pinfunction "2_2") (pintype "passive"))
      (node (ref "C38") (pin "2") (pinfunction "2_2") (pintype "passive"))
      (node (ref "C39") (pin "2") (pinfunction "2_2") (pintype "passive"))
      (node (ref "C4") (pin "2") (pinfunction "2_2") (pintype "passive"))
      (node (ref "C40") (pin "2") (pinfunction "2_2") (pintype "passive"))
      (node (ref "C41") (pin "2") (pinfunction "2_2") (pintype "passive"))
      (node (ref "C5") (pin "2") (pinfunction "2_2") (pintype "passive"))
      (node (ref "C53") (pin "2") (pinfunction "2_2") (pintype "passive"))
      (node (ref "C54") (pin "2") (pinfunction "2_2") (pintype "passive"))
      (node (ref "C55") (pin "2") (pinfunction "2_2") (pintype "passive"))
      (node (ref "C56") (pin "2") (pinfunction "2_2") (pintype "passive"))
      (node (ref "C7") (pin "1") (pinfunction "1_1") (pintype "passive"))
      (node (ref "D2") (pin "1") (pinfunction "K_1") (pintype "passive"))
      (node (ref "Q1") (pin "5") (pinfunction "D_5") (pintype "passive"))
      (node (ref "R23") (pin "2") (pinfunction "2_2") (pintype "passive"))
      (node (ref "R27") (pin "2") (pinfunction "2_2") (pintype "passive"))
      (node (ref "R3") (pin "1") (pinfunction "1_1") (pintype "passive"))
      (node (ref "R4") (pin "2") (pinfunction "2_2") (pintype "passive"))
      (node (ref "U1") (pin "1") (pinfunction "VIN_1") (pintype "passive"))
      (node (ref "U2") (pin "2") (pinfunction "VIN_2") (pintype "passive"))
      (node (ref "U3") (pin "2") (pinfunction "VIN_2") (pintype "passive"))
      (node (ref "Vin1") (pin "1") (pinfunction "+_1") (pintype "passive"))
    )
  )
)
